# NguyenLyPhatHongNgoai.net
KiCad netlist of a schematic drawn in Altium Designer
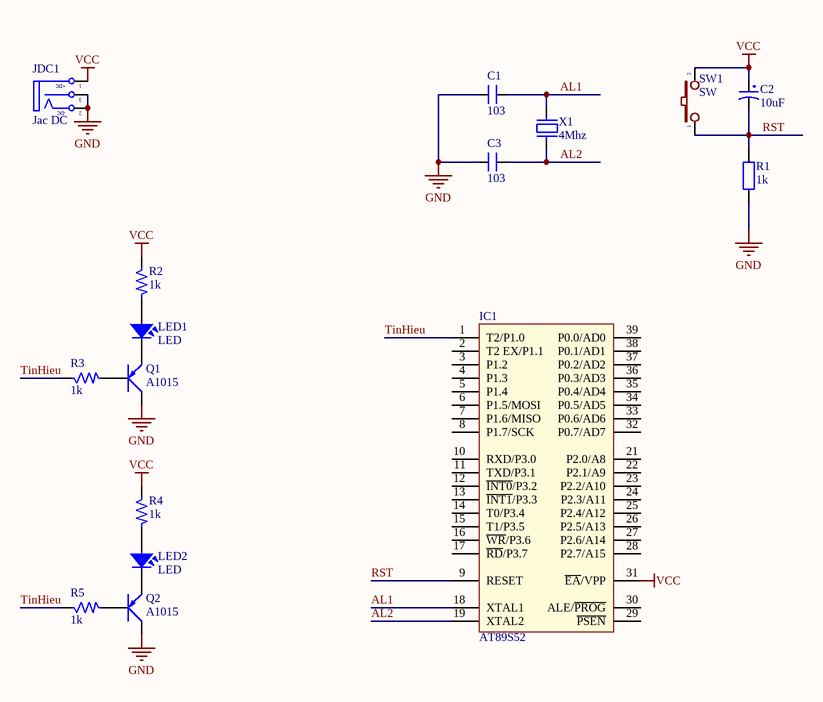
[diagram p0: NguyenLyPhatHongNgoai.SchDoc]

(export (version "E")
  (design (tool "Eeschema 10.0.6"))
  (components
    (comp (ref "C1")
      (value "103")
      (footprint "CN1.5")
      (description "Cap np 682pF => 104pF")
      (libsource (lib "Tr.Thoai") (part "CN1.5"))
    )
    (comp (ref "C2")
      (value "10uF")
      (footprint "CP1/2")
      (description "Cap P  0,1uF < 22uF , 16 - 50V")
      (libsource (lib "syhaunguyen") (part "CP1"))
    )
    (comp (ref "C3")
      (value "103")
      (footprint "CN1.5")
      (description "Cap np 682pF => 104pF")
      (libsource (lib "Tr.Thoai") (part "CN1.5"))
    )
    (comp (ref "IC1")
      (value "AT89S52")
      (footprint "DIP40/W0.6")
      (description "AT89S52, 8k Byte Flash Memory , 40 Pin")
      (libsource (lib "syhaunguyen") (part "AT89S52"))
    )
    (comp (ref "JDC1")
      (value "Jac DC")
      (footprint "DC-IN")
      (description "Jac DC input")
      (libsource (lib "Tr.Thoai") (part "JACK DC"))
    )
    (comp (ref "LED1")
      (value "LED")
      (footprint "LED-5TRED")
      (description "LED Single colour Green and Red")
      (libsource (lib "syhaunguyen") (part "LED"))
    )
    (comp (ref "LED2")
      (value "LED")
      (footprint "LED-5TRED")
      (description "LED Single colour Green and Red")
      (libsource (lib "syhaunguyen") (part "LED"))
    )
    (comp (ref "Q1")
      (value "A1015")
      (footprint "QTO-92")
      (description "PNP 600mW, ECB")
      (libsource (lib "syhaunguyen") (part "A1015"))
    )
    (comp (ref "Q2")
      (value "A1015")
      (footprint "QTO-92")
      (description "PNP 600mW, ECB")
      (libsource (lib "syhaunguyen") (part "A1015"))
    )
    (comp (ref "R1")
      (value "1k")
      (footprint "R1/2W4")
      (description "Resistor 1/4W")
      (libsource (lib "Tr.Thoai") (part "R1/4W"))
    )
    (comp (ref "R2")
      (value "1k")
      (footprint "R1/4W")
      (description "Resistor 1/4W")
      (libsource (lib "syhaunguyen") (part "R"))
    )
    (comp (ref "R3")
      (value "1k")
      (footprint "R1/4W")
      (description "Resistor 1/4W")
      (libsource (lib "syhaunguyen") (part "R"))
    )
    (comp (ref "R4")
      (value "1k")
      (footprint "R1/4W")
      (description "Resistor 1/4W")
      (libsource (lib "syhaunguyen") (part "R"))
    )
    (comp (ref "R5")
      (value "1k")
      (footprint "R1/4W")
      (description "Resistor 1/4W")
      (libsource (lib "syhaunguyen") (part "R"))
    )
    (comp (ref "SW1")
      (value "SW")
      (footprint "SW2")
      (description "Switch button 2 pin")
      (libsource (lib "Tr.Thoai") (part "SW2"))
    )
    (comp (ref "X1")
      (value "4Mhz")
      (footprint "XT2")
      (description "Crystal For all Crystal 2pin.")
      (libsource (lib "Tr.Thoai") (part "XT2"))
    )
  )
  (nets
    (net (code "1") (name "/AL1") (class "Default")
      (node (ref "C1") (pin "2") (pinfunction "2_2") (pintype "passive"))
      (node (ref "IC1") (pin "18") (pinfunction "XTAL1_18") (pintype "passive"))
      (node (ref "X1") (pin "2") (pinfunction "2_2") (pintype "passive"))
    )
    (net (code "2") (name "/AL2") (class "Default")
      (node (ref "C3") (pin "2") (pinfunction "2_2") (pintype "passive"))
      (node (ref "IC1") (pin "19") (pinfunction "XTAL2_19") (pintype "passive"))
      (node (ref "X1") (pin "1") (pinfunction "1_1") (pintype "passive"))
    )
    (net (code "3") (name "/RST") (class "Default")
      (node (ref "C2") (pin "2") (pinfunction "2_2") (pintype "passive"))
      (node (ref "IC1") (pin "9") (pinfunction "RESET_9") (pintype "passive"))
      (node (ref "R1") (pin "2") (pinfunction "2_2") (pintype "passive"))
      (node (ref "SW1") (pin "1") (pinfunction "1_1") (pintype "passive"))
    )
    (net (code "4") (name "/TinHieu") (class "Default")
      (node (ref "IC1") (pin "1") (pinfunction "T2/P1.0_1") (pintype "passive"))
      (node (ref "R3") (pin "1") (pinfunction "1_1") (pintype "passive"))
      (node (ref "R5") (pin "1") (pinfunction "1_1") (pintype "passive"))
    )
    (net (code "5") (name "GND") (class "Default")
      (node (ref "C1") (pin "1") (pinfunction "1_1") (pintype "passive"))
      (node (ref "C3") (pin "1") (pinfunction "1_1") (pintype "passive"))
      (node (ref "IC1") (pin "20") (pinfunction "GND_20") (pintype "power_in"))
      (node (ref "JDC1") (pin "2") (pinfunction "TN_2") (pintype "passive"))
      (node (ref "JDC1") (pin "3") (pinfunction "S_3") (pintype "power_in"))
      (node (ref "Q1") (pin "2") (pinfunction "C_2") (pintype "passive"))
      (node (ref "Q2") (pin "2") (pinfunction "C_2") (pintype "passive"))
      (node (ref "R1") (pin "1") (pinfunction "1_1") (pintype "passive"))
    )
    (net (code "6") (name "Net-(LED1-Pad1)") (class "Default")
      (node (ref "LED1") (pin "1") (pinfunction "1_1") (pintype "passive"))
      (node (ref "R2") (pin "2") (pinfunction "2_2") (pintype "passive"))
    )
    (net (code "7") (name "Net-(LED2-Pad1)") (class "Default")
      (node (ref "LED2") (pin "1") (pinfunction "1_1") (pintype "passive"))
      (node (ref "R4") (pin "2") (pinfunction "2_2") (pintype "passive"))
    )
    (net (code "8") (name "Net-(Q1-B)") (class "Default")
      (node (ref "Q1") (pin "3") (pinfunction "B_3") (pintype "passive"))
      (node (ref "R3") (pin "2") (pinfunction "2_2") (pintype "passive"))
    )
    (net (code "9") (name "Net-(Q1-E)") (class "Default")
      (node (ref "LED1") (pin "2") (pinfunction "2_2") (pintype "passive"))
      (node (ref "Q1") (pin "1") (pinfunction "E_1") (pintype "passive"))
    )
    (net (code "10") (name "Net-(Q2-B)") (class "Default")
      (node (ref "Q2") (pin "3") (pinfunction "B_3") (pintype "passive"))
      (node (ref "R5") (pin "2") (pinfunction "2_2") (pintype "passive"))
    )
    (net (code "11") (name "Net-(Q2-E)") (class "Default")
      (node (ref "LED2") (pin "2") (pinfunction "2_2") (pintype "passive"))
      (node (ref "Q2") (pin "1") (pinfunction "E_1") (pintype "passive"))
    )
    (net (code "12") (name "VCC") (class "Default")
      (node (ref "C2") (pin "1") (pinfunction "1_1") (pintype "passive"))
      (node (ref "IC1") (pin "31") (pinfunction "~{EA}/VPP_31") (pintype "passive"))
      (node (ref "IC1") (pin "40") (pinfunction "VCC_40") (pintype "power_in"))
      (node (ref "JDC1") (pin "1") (pinfunction "T_1") (pintype "passive"))
      (node (ref "R2") (pin "1") (pinfunction "1_1") (pintype "passive"))
      (node (ref "R4") (pin "1") (pinfunction "1_1") (pintype "passive"))
      (node (ref "SW1") (pin "2") (pinfunction "2_2") (pintype "passive"))
    )
    (net (code "13") (name "unconnected-(IC1-ALE{slash}~{PROG}-Pad30)") (class "Default")
      (node (ref "IC1") (pin "30") (pinfunction "ALE/~{PROG}_30") (pintype "passive"))
    )
    (net (code "14") (name "unconnected-(IC1-P0.0{slash}AD0-Pad39)") (class "Default")
      (node (ref "IC1") (pin "39") (pinfunction "P0.0/AD0_39") (pintype "passive"))
    )
    (net (code "15") (name "unconnected-(IC1-P0.1{slash}AD1-Pad38)") (class "Default")
      (node (ref "IC1") (pin "38") (pinfunction "P0.1/AD1_38") (pintype "passive"))
    )
    (net (code "16") (name "unconnected-(IC1-P0.2{slash}AD2-Pad37)") (class "Default")
      (node (ref "IC1") (pin "37") (pinfunction "P0.2/AD2_37") (pintype "passive"))
    )
    (net (code "17") (name "unconnected-(IC1-P0.3{slash}AD3-Pad36)") (class "Default")
      (node (ref "IC1") (pin "36") (pinfunction "P0.3/AD3_36") (pintype "passive"))
    )
    (net (code "18") (name "unconnected-(IC1-P0.4{slash}AD4-Pad35)") (class "Default")
      (node (ref "IC1") (pin "35") (pinfunction "P0.4/AD4_35") (pintype "passive"))
    )
    (net (code "19") (name "unconnected-(IC1-P0.5{slash}AD5-Pad34)") (class "Default")
      (node (ref "IC1") (pin "34") (pinfunction "P0.5/AD5_34") (pintype "passive"))
    )
    (net (code "20") (name "unconnected-(IC1-P0.6{slash}AD6-Pad33)") (class "Default")
      (node (ref "IC1") (pin "33") (pinfunction "P0.6/AD6_33") (pintype "passive"))
    )
    (net (code "21") (name "unconnected-(IC1-P0.7{slash}AD7-Pad32)") (class "Default")
      (node (ref "IC1") (pin "32") (pinfunction "P0.7/AD7_32") (pintype "passive"))
    )
    (net (code "22") (name "unconnected-(IC1-P1.2-Pad3)") (class "Default")
      (node (ref "IC1") (pin "3") (pinfunction "P1.2_3") (pintype "passive"))
    )
    (net (code "23") (name "unconnected-(IC1-P1.3-Pad4)") (class "Default")
      (node (ref "IC1") (pin "4") (pinfunction "P1.3_4") (pintype "passive"))
    )
    (net (code "24") (name "unconnected-(IC1-P1.4-Pad5)") (class "Default")
      (node (ref "IC1") (pin "5") (pinfunction "P1.4_5") (pintype "passive"))
    )
    (net (code "25") (name "unconnected-(IC1-P1.5{slash}MOSI-Pad6)") (class "Default")
      (node (ref "IC1") (pin "6") (pinfunction "P1.5/MOSI_6") (pintype "passive"))
    )
    (net (code "26") (name "unconnected-(IC1-P1.6{slash}MISO-Pad7)") (class "Default")
      (node (ref "IC1") (pin "7") (pinfunction "P1.6/MISO_7") (pintype "passive"))
    )
    (net (code "27") (name "unconnected-(IC1-P1.7{slash}SCK-Pad8)") (class "Default")
      (node (ref "IC1") (pin "8") (pinfunction "P1.7/SCK_8") (pintype "passive"))
    )
    (net (code "28") (name "unconnected-(IC1-P2.0{slash}A8-Pad21)") (class "Default")
      (node (ref "IC1") (pin "21") (pinfunction "P2.0/A8_21") (pintype "passive"))
    )
    (net (code "29") (name "unconnected-(IC1-P2.1{slash}A9-Pad22)") (class "Default")
      (node (ref "IC1") (pin "22") (pinfunction "P2.1/A9_22") (pintype "passive"))
    )
    (net (code "30") (name "unconnected-(IC1-P2.2{slash}A10-Pad23)") (class "Default")
      (node (ref "IC1") (pin "23") (pinfunction "P2.2/A10_23") (pintype "passive"))
    )
    (net (code "31") (name "unconnected-(IC1-P2.3{slash}A11-Pad24)") (class "Default")
      (node (ref "IC1") (pin "24") (pinfunction "P2.3/A11_24") (pintype "passive"))
    )
    (net (code "32") (name "unconnected-(IC1-P2.4{slash}A12-Pad25)") (class "Default")
      (node (ref "IC1") (pin "25") (pinfunction "P2.4/A12_25") (pintype "passive"))
    )
    (net (code "33") (name "unconnected-(IC1-P2.5{slash}A13-Pad26)") (class "Default")
      (node (ref "IC1") (pin "26") (pinfunction "P2.5/A13_26") (pintype "passive"))
    )
    (net (code "34") (name "unconnected-(IC1-P2.6{slash}A14-Pad27)") (class "Default")
      (node (ref "IC1") (pin "27") (pinfunction "P2.6/A14_27") (pintype "passive"))
    )
    (net (code "35") (name "unconnected-(IC1-P2.7{slash}A15-Pad28)") (class "Default")
      (node (ref "IC1") (pin "28") (pinfunction "P2.7/A15_28") (pintype "passive"))
    )
    (net (code "36") (name "unconnected-(IC1-RXD{slash}P3.0-Pad10)") (class "Default")
      (node (ref "IC1") (pin "10") (pinfunction "RXD/P3.0_10") (pintype "passive"))
    )
    (net (code "37") (name "unconnected-(IC1-T0{slash}P3.4-Pad14)") (class "Default")
      (node (ref "IC1") (pin "14") (pinfunction "T0/P3.4_14") (pintype "passive"))
    )
    (net (code "38") (name "unconnected-(IC1-T1{slash}P3.5-Pad15)") (class "Default")
      (node (ref "IC1") (pin "15") (pinfunction "T1/P3.5_15") (pintype "passive"))
    )
    (net (code "39") (name "unconnected-(IC1-T2_EX{slash}P1.1-Pad2)") (class "Default")
      (node (ref "IC1") (pin "2") (pinfunction "T2_EX/P1.1_2") (pintype "passive"))
    )
    (net (code "40") (name "unconnected-(IC1-TXD{slash}P3.1-Pad11)") (class "Default")
      (node (ref "IC1") (pin "11") (pinfunction "TXD/P3.1_11") (pintype "passive"))
    )
    (net (code "41") (name "unconnected-(IC1-~{INT0}{slash}P3.2-Pad12)") (class "Default")
      (node (ref "IC1") (pin "12") (pinfunction "~{INT0}/P3.2_12") (pintype "passive"))
    )
    (net (code "42") (name "unconnected-(IC1-~{INT1}{slash}P3.3-Pad13)") (class "Default")
      (node (ref "IC1") (pin "13") (pinfunction "~{INT1}/P3.3_13") (pintype "passive"))
    )
    (net (code "43") (name "unconnected-(IC1-~{PSEN}-Pad29)") (class "Default")
      (node (ref "IC1") (pin "29") (pinfunction "~{PSEN}_29") (pintype "passive"))
    )
    (net (code "44") (name "unconnected-(IC1-~{RD}{slash}P3.7-Pad17)") (class "Default")
      (node (ref "IC1") (pin "17") (pinfunction "~{RD}/P3.7_17") (pintype "passive"))
    )
    (net (code "45") (name "unconnected-(IC1-~{WR}{slash}P3.6-Pad16)") (class "Default")
      (node (ref "IC1") (pin "16") (pinfunction "~{WR}/P3.6_16") (pintype "passive"))
    )
  )
)
